# PSU.net
KiCad netlist of a schematic drawn in Altium Designer
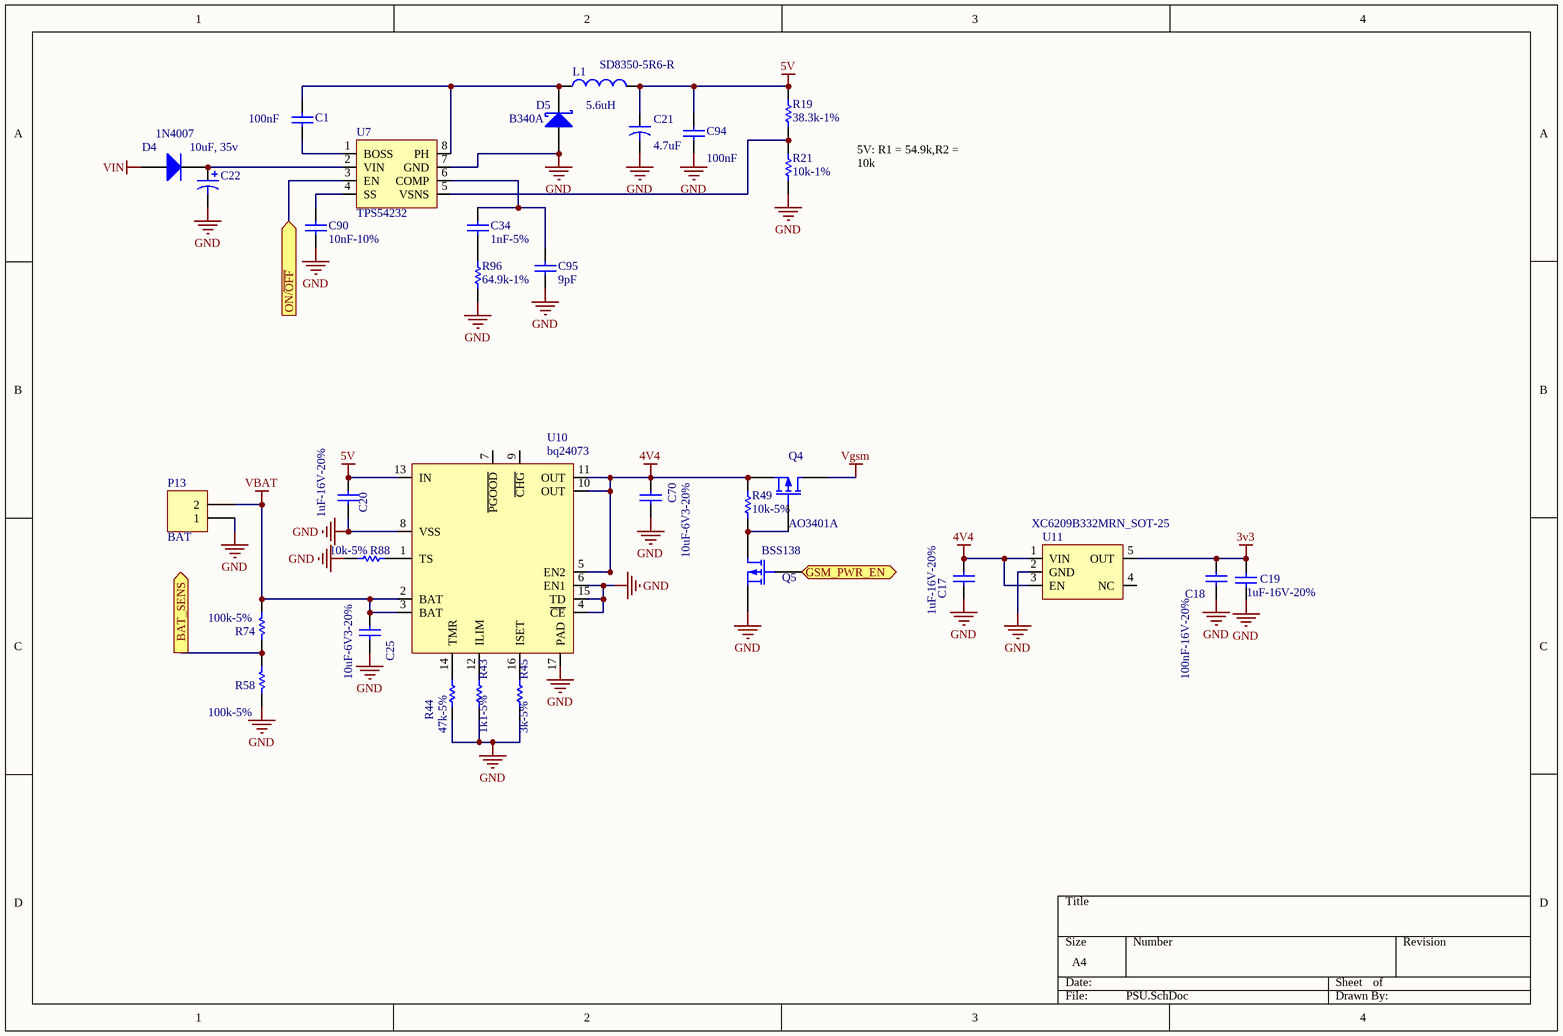
[diagram p0: PSU.SchDoc]

(export (version "E")
  (design (tool "Eeschema 10.0.6"))
  (components
    (comp (ref "C1")
      (value "100nF")
      (footprint "C0402")
      (description "Capacitor")
      (fields (field (name "PUBLISHER") "Altium Limited"))
      (libsource (lib "Miscellaneous Devices") (part "Cap"))
    )
    (comp (ref "C17")
      (value "1uF-16V-20%")
      (footprint "C0603")
      (description "CAP CER 1UF 16V Y5V 0603")
      (fields
        (field (name "MANUFACTURER") "Yageo")
        (field (name "DIGI-KEY PART NUMBER") "311-1372-1-ND")
        (field (name "PUBLISHER") "Altium Limited")
      )
      (libsource (lib "Miscellaneous Devices") (part "Cap"))
    )
    (comp (ref "C18")
      (value "100nF-16V-20%")
      (footprint "C0402")
      (description "CAP CER 0.1UF 16V Y5V 0402")
      (fields
        (field (name "MANUFACTURER") "Yageo")
        (field (name "DIGI-KEY PART NUMBER") "311-1047-1-ND")
        (field (name "PUBLISHER") "Altium Limited")
      )
      (libsource (lib "Miscellaneous Devices") (part "Cap"))
    )
    (comp (ref "C19")
      (value "1uF-16V-20%")
      (footprint "C0603")
      (description "CAP CER 1UF 16V Y5V 0603")
      (fields
        (field (name "MANUFACTURER") "Yageo")
        (field (name "DIGI-KEY PART NUMBER") "311-1372-1-ND")
        (field (name "PUBLISHER") "Altium Limited")
      )
      (libsource (lib "Miscellaneous Devices") (part "Cap"))
    )
    (comp (ref "C20")
      (value "1uF-16V-20%")
      (footprint "C0603")
      (description "CAP CER 1UF 16V Y5V 0603")
      (fields
        (field (name "MANUFACTURER") "Yageo")
        (field (name "DIGI-KEY PART NUMBER") "311-1372-1-ND")
        (field (name "PUBLISHER") "Altium Limited")
      )
      (libsource (lib "Miscellaneous Devices") (part "Cap"))
    )
    (comp (ref "C21")
      (value "4.7uF")
      (footprint "C1206")
      (description "Capacitor")
      (fields (field (name "PUBLISHER") "Altium Limited"))
      (libsource (lib "Miscellaneous Devices") (part "Cap2"))
    )
    (comp (ref "C22")
      (value "10uF, 35v")
      (footprint "CAPACITOR SIZE_C(D5.3)")
      (description "CAP ALUM 10UF 35V 20% SMD")
      (fields
        (field (name "DIGI-KEY PART NUMBER") "PCE3947TR-ND")
        (field (name "MANUFACTURER") "Panasonic Electronic Components")
        (field (name "PUBLISHER") "Altium Limited")
      )
      (libsource (lib "Miscellaneous Devices") (part "Cap Pol3"))
    )
    (comp (ref "C25")
      (value "10uF-6V3-20%")
      (footprint "C0603")
      (description "CAP CER 10UF 6.3V 20% X5R 0603")
      (fields
        (field (name "MANUFACTURER") "Yageo")
        (field (name "DIGI-KEY PART NUMBER") "311-1448-1-ND")
        (field (name "PUBLISHER") "Altium Limited")
      )
      (libsource (lib "Miscellaneous Devices") (part "Cap"))
    )
    (comp (ref "C34")
      (value "1nF-5%")
      (footprint "C0402")
      (description "Non-Polarized Capacitor")
      (fields (field (name "DIGI-KEY PART NUMBER") "311-1122-1-ND") (field (name "MANUFACTURER") "Yageo"))
      (libsource (lib "Capacitor") (part "1nF-50V-C0805"))
    )
    (comp (ref "C70")
      (value "10uF-6V3-20%")
      (footprint "C0603")
      (description "CAP CER 10UF 6.3V 20% X5R 0603")
      (fields
        (field (name "MANUFACTURER") "Yageo")
        (field (name "DIGI-KEY PART NUMBER") "311-1448-1-ND")
        (field (name "PUBLISHER") "Altium Limited")
      )
      (libsource (lib "Miscellaneous Devices") (part "Cap"))
    )
    (comp (ref "C90")
      (value "10nF-10%")
      (footprint "C0402")
      (description "Non-Polarized Capacitor")
      (fields (field (name "DIGI-KEY PART NUMBER") "311-1136-1-ND") (field (name "MANUFACTURER") "Yageo"))
      (libsource (lib "Capacitor") (part "10nF-50V-C0805"))
    )
    (comp (ref "C94")
      (value "100nF")
      (footprint "C0402")
      (description "Capacitor")
      (fields (field (name "PUBLISHER") "Altium Limited"))
      (libsource (lib "Miscellaneous Devices") (part "Cap"))
    )
    (comp (ref "C95")
      (value "9pF")
      (footprint "C0402")
      (description "Non-Polarized Capacitor")
      (fields (field (name "DIGI-KEY PART NUMBER") "311-1098-1-ND") (field (name "MANUFACTURER") "Yageo"))
      (libsource (lib "Capacitor") (part "9pF-50V-C0805"))
    )
    (comp (ref "D4")
      (value "1N4007")
      (footprint "DO-214AC (SMA)")
      (description "DIODE GEN PURPOSE 1000V 1A SMA")
      (fields
        (field (name "DIGI-KEY PART NUMBER") "641-1018-1-ND")
        (field (name "MANUFACTURER PART NUMBER") "CGRA4007-G")
        (field (name "PUBLISHER") "Altium Limited")
      )
      (libsource (lib "Miscellaneous Devices") (part "Diode"))
    )
    (comp (ref "D5")
      (value "B340A")
      (footprint "DO-214AC (SMA)")
      (description "DIODE SCHOTTKY 40V 3A SMA")
      (fields
        (field (name "DIGI-KEY PART NUMBER") "B340A-E3/61TGITR-ND")
        (field (name "MANUFACTURER PART NUMBER") "B340A-E3/61T")
        (field (name "PUBLISHER") "Altium Limited")
      )
      (libsource (lib "Miscellaneous Devices") (part "D Schottky"))
    )
    (comp (ref "L1")
      (value "SD8350-5R6-R")
      (footprint "SD8350-5R6-R")
      (description "Digikey part SD8350-4R7-R")
      (fields (field (name "ALTIUM_VALUE") "5.6uH") (field (name "PUBLISHER") "Altium Limited"))
      (libsource (lib "Miscellaneous Devices") (part "Inductor"))
    )
    (comp (ref "P13")
      (value "BAT")
      (footprint "HDR1X2")
      (description "Header, 2-Pin")
      (fields (field (name "PUBLISHER") "Altium Limited"))
      (libsource (lib "Miscellaneous Connectors") (part "Header 2"))
    )
    (comp (ref "Q4")
      (value "AO3401A")
      (footprint "SOT23-3")
      (description "MOSFET P-CH -30V -4.3A SOT23")
      (fields
        (field (name "DIGI-KEY PART NUMBER") "785-1001-1-ND")
        (field (name "MANUFACTURER") "Alpha & Omega Semiconductor Inc")
        (field (name "PUBLISHER") "Altium Limited")
      )
      (libsource (lib "") (part "MOSFET-P_1"))
    )
    (comp (ref "Q5")
      (value "BSS138")
      (footprint "SOT23-3")
      (description "MOSFET N-CH 50V 200MA SOT23-3")
      (fields
        (field (name "DIGI-KEY PART NUMBER") "BSS138-FDICT-ND")
        (field (name "MANUFACTURER") "Diodes Inc")
        (field (name "PUBLISHER") "Altium Limited")
      )
      (libsource (lib "Miscellaneous Devices") (part "MOSFET-P"))
    )
    (comp (ref "R19")
      (value "38.3k-1%")
      (footprint "R0402")
      (description "RES 38.3k OHM 1/4W 1% 0805 SMD")
      (fields (field (name "DIGI-KEY PART NUMBER") "311-38.3KCRTR-ND") (field (name "MANUFACTURER") "Yageo"))
      (libsource (lib "All_Resistor") (part "38.3k-1%-R0805"))
    )
    (comp (ref "R21")
      (value "10k-1%")
      (footprint "R0402")
      (description "RES 10k OHM 1/4W 1% 0805 SMD")
      (fields (field (name "DIGI-KEY PART NUMBER") "311-10.0KCRTR-ND") (field (name "MANUFACTURER") "Yageo"))
      (libsource (lib "All_Resistor") (part "10k-1%-R0805"))
    )
    (comp (ref "R43")
      (value "1k1-5%")
      (footprint "R0402")
      (description "RES 1.1K OHM 1/16W 5% 0402 SMD")
      (fields
        (field (name "DIGI-KEY PART NUMBER") "311-1.1KJRCT-ND")
        (field (name "MANUFACTURER") "Yageo")
        (field (name "PUBLISHER") "Altium Limited")
      )
      (libsource (lib "Miscellaneous Devices") (part "Res1"))
    )
    (comp (ref "R44")
      (value "47k-5%")
      (footprint "R0402")
      (description "RES 47K OHM 1/16W 5% 0402 SMD")
      (fields
        (field (name "DIGI-KEY PART NUMBER") "311-47KJRCT-ND")
        (field (name "MANUFACTURER") "Yageo")
        (field (name "PUBLISHER") "Altium Limited")
      )
      (libsource (lib "Miscellaneous Devices") (part "Res1"))
    )
    (comp (ref "R45")
      (value "3k-5%")
      (footprint "R0402")
      (description "RES 1.5K OHM 1/16W 5% 0402 SMD")
      (fields
        (field (name "DIGI-KEY PART NUMBER") "311-3.0KJRCT-ND")
        (field (name "MANUFACTURER") "Yageo")
        (field (name "PUBLISHER") "Altium Limited")
      )
      (libsource (lib "Miscellaneous Devices") (part "Res1"))
    )
    (comp (ref "R49")
      (value "10k-5%")
      (footprint "R0402")
      (description "RES 10K OHM 1/16W 5% 0402 SMD")
      (fields
        (field (name "DIGI-KEY PART NUMBER") "311-10KJRCT-ND")
        (field (name "MANUFACTURER") "Yageo")
        (field (name "PUBLISHER") "Altium Limited")
      )
      (libsource (lib "Miscellaneous Devices") (part "Res1"))
    )
    (comp (ref "R58")
      (value "100k-5%")
      (footprint "R0402")
      (description "RES 100K OHM 1/16W 5% 0402 SMD")
      (fields
        (field (name "DIGI-KEY PART NUMBER") "311-100KJRCT-ND")
        (field (name "MANUFACTURER") "Yageo")
        (field (name "PUBLISHER") "Altium Limited")
      )
      (libsource (lib "Miscellaneous Devices") (part "Res1"))
    )
    (comp (ref "R74")
      (value "100k-5%")
      (footprint "R0402")
      (description "RES 100K OHM 1/16W 5% 0402 SMD")
      (fields
        (field (name "DIGI-KEY PART NUMBER") "311-100KJRCT-ND")
        (field (name "MANUFACTURER") "Yageo")
        (field (name "PUBLISHER") "Altium Limited")
      )
      (libsource (lib "Miscellaneous Devices") (part "Res1"))
    )
    (comp (ref "R88")
      (value "10k-5%")
      (footprint "R0402")
      (description "RES 10K OHM 1/16W 5% 0402 SMD")
      (fields
        (field (name "DIGI-KEY PART NUMBER") "311-10KJRCT-ND")
        (field (name "MANUFACTURER") "Yageo")
        (field (name "PUBLISHER") "Altium Limited")
      )
      (libsource (lib "Miscellaneous Devices") (part "Res1"))
    )
    (comp (ref "R96")
      (value "64.9k-1%")
      (footprint "R0402")
      (description "RES 64.9k OHM 1/4W 1% 0805 SMD")
      (fields (field (name "DIGI-KEY PART NUMBER") "311-64.9KCRTR-ND") (field (name "MANUFACTURER") "Yageo"))
      (libsource (lib "All_Resistor") (part "64.9k-1%-R0805"))
    )
    (comp (ref "U7")
      (value "TPS54232")
      (footprint "SOIC127P600-8AL")
      (libsource (lib "TPS54232") (part "Component_1"))
    )
    (comp (ref "U10")
      (value "bq24073")
      (footprint "pq24073")
      (description "IC LI-ION CHARGE/PWR MGMT 16-QFN")
      (fields
        (field (name "DIGI-KEY PART NUMBER") "296-23839-1-ND")
        (field (name "MANUFACTURER") "Texas Instruments")
      )
      (libsource (lib "TI_Power") (part "BATTERY_CHARGER"))
    )
    (comp (ref "U11")
      (value "XC6209B332MRN_SOT-25")
      (footprint "SOT23-5")
      (fields (field (name "MANUFACTURER") "Tyrone"))
      (libsource (lib "Schlib1") (part "XC6209B332MRN_SOT-25"))
    )
  )
  (nets
    (net (code "1") (name "/BAT_SENS") (class "Default")
      (node (ref "R58") (pin "2") (pinfunction "2_2") (pintype "passive"))
      (node (ref "R74") (pin "1") (pinfunction "1_1") (pintype "passive"))
    )
    (net (code "2") (name "/GSM_PWR_EN") (class "Default")
      (node (ref "Q5") (pin "1") (pinfunction "G_1") (pintype "passive"))
    )
    (net (code "3") (name "/ON{slash}~{OFF}") (class "Default")
      (node (ref "U7") (pin "3") (pinfunction "EN_3") (pintype "passive"))
    )
    (net (code "4") (name "3v3") (class "Default")
      (node (ref "C18") (pin "2") (pinfunction "2_2") (pintype "passive"))
      (node (ref "C19") (pin "1") (pinfunction "1_1") (pintype "passive"))
      (node (ref "U11") (pin "5") (pinfunction "OUT_5") (pintype "passive"))
    )
    (net (code "5") (name "4V4") (class "Default")
      (node (ref "C17") (pin "1") (pinfunction "1_1") (pintype "passive"))
      (node (ref "C70") (pin "2") (pinfunction "2_2") (pintype "passive"))
      (node (ref "Q4") (pin "2") (pinfunction "S_2") (pintype "passive"))
      (node (ref "R49") (pin "1") (pinfunction "1_1") (pintype "passive"))
      (node (ref "U10") (pin "10") (pinfunction "OUT_10") (pintype "passive"))
      (node (ref "U10") (pin "11") (pinfunction "OUT_11") (pintype "passive"))
      (node (ref "U10") (pin "5") (pinfunction "EN2_5") (pintype "passive"))
      (node (ref "U11") (pin "1") (pinfunction "VIN_1") (pintype "passive"))
      (node (ref "U11") (pin "3") (pinfunction "EN_3") (pintype "passive"))
    )
    (net (code "6") (name "5V") (class "Default")
      (node (ref "C20") (pin "2") (pinfunction "2_2") (pintype "passive"))
      (node (ref "C21") (pin "1") (pinfunction "1_1") (pintype "passive"))
      (node (ref "C94") (pin "2") (pinfunction "2_2") (pintype "passive"))
      (node (ref "L1") (pin "2") (pinfunction "2_2") (pintype "passive"))
      (node (ref "R19") (pin "2") (pinfunction "2_2") (pintype "passive"))
      (node (ref "U10") (pin "13") (pinfunction "IN_13") (pintype "passive"))
    )
    (net (code "7") (name "GND") (class "Default")
      (node (ref "C17") (pin "2") (pinfunction "2_2") (pintype "passive"))
      (node (ref "C18") (pin "1") (pinfunction "1_1") (pintype "passive"))
      (node (ref "C19") (pin "2") (pinfunction "2_2") (pintype "passive"))
      (node (ref "C20") (pin "1") (pinfunction "1_1") (pintype "passive"))
      (node (ref "C21") (pin "2") (pinfunction "2_2") (pintype "passive"))
      (node (ref "C22") (pin "2") (pinfunction "2_2") (pintype "passive"))
      (node (ref "C25") (pin "1") (pinfunction "1_1") (pintype "passive"))
      (node (ref "C70") (pin "1") (pinfunction "1_1") (pintype "passive"))
      (node (ref "C90") (pin "1") (pinfunction "1_1") (pintype "passive"))
      (node (ref "C94") (pin "1") (pinfunction "1_1") (pintype "passive"))
      (node (ref "C95") (pin "1") (pinfunction "1_1") (pintype "passive"))
      (node (ref "D5") (pin "1") (pinfunction "A_1") (pintype "passive"))
      (node (ref "P13") (pin "1") (pinfunction "1_1") (pintype "passive"))
      (node (ref "Q5") (pin "2") (pinfunction "S_2") (pintype "passive"))
      (node (ref "R21") (pin "1") (pinfunction "1_1") (pintype "passive"))
      (node (ref "R43") (pin "2") (pinfunction "2_2") (pintype "passive"))
      (node (ref "R44") (pin "2") (pinfunction "2_2") (pintype "passive"))
      (node (ref "R45") (pin "2") (pinfunction "2_2") (pintype "passive"))
      (node (ref "R58") (pin "1") (pinfunction "1_1") (pintype "passive"))
      (node (ref "R88") (pin "2") (pinfunction "2_2") (pintype "passive"))
      (node (ref "R96") (pin "1") (pinfunction "1_1") (pintype "passive"))
      (node (ref "U10") (pin "15") (pinfunction "TD_15") (pintype "passive"))
      (node (ref "U10") (pin "17") (pinfunction "PAD_17") (pintype "passive"))
      (node (ref "U10") (pin "4") (pinfunction "~{CE}_4") (pintype "passive"))
      (node (ref "U10") (pin "6") (pinfunction "EN1_6") (pintype "passive"))
      (node (ref "U10") (pin "8") (pinfunction "VSS_8") (pintype "passive"))
      (node (ref "U11") (pin "2") (pinfunction "GND_2") (pintype "passive"))
      (node (ref "U7") (pin "7") (pinfunction "GND_7") (pintype "passive"))
    )
    (net (code "8") (name "Net-(C34-Pad1)") (class "Default")
      (node (ref "C34") (pin "1") (pinfunction "1_1") (pintype "passive"))
      (node (ref "R96") (pin "2") (pinfunction "2_2") (pintype "passive"))
    )
    (net (code "9") (name "Net-(D4-K)") (class "Default")
      (node (ref "C22") (pin "1") (pinfunction "1_1") (pintype "passive"))
      (node (ref "D4") (pin "2") (pinfunction "K_2") (pintype "passive"))
      (node (ref "U7") (pin "2") (pinfunction "VIN_2") (pintype "passive"))
    )
    (net (code "10") (name "Net-(D5-K)") (class "Default")
      (node (ref "C1") (pin "1") (pinfunction "1_1") (pintype "passive"))
      (node (ref "D5") (pin "2") (pinfunction "K_2") (pintype "passive"))
      (node (ref "L1") (pin "1") (pinfunction "1_1") (pintype "passive"))
      (node (ref "U7") (pin "8") (pinfunction "PH_8") (pintype "passive"))
    )
    (net (code "11") (name "Net-(Q4-G)") (class "Default")
      (node (ref "Q4") (pin "1") (pinfunction "G_1") (pintype "passive"))
      (node (ref "Q5") (pin "3") (pinfunction "D_3") (pintype "passive"))
      (node (ref "R49") (pin "2") (pinfunction "2_2") (pintype "passive"))
    )
    (net (code "12") (name "Net-(U7-BOSS)") (class "Default")
      (node (ref "C1") (pin "2") (pinfunction "2_2") (pintype "passive"))
      (node (ref "U7") (pin "1") (pinfunction "BOSS_1") (pintype "passive"))
    )
    (net (code "13") (name "Net-(U7-COMP)") (class "Default")
      (node (ref "C34") (pin "2") (pinfunction "2_2") (pintype "passive"))
      (node (ref "C95") (pin "2") (pinfunction "2_2") (pintype "passive"))
      (node (ref "U7") (pin "6") (pinfunction "COMP_6") (pintype "passive"))
    )
    (net (code "14") (name "Net-(U7-SS)") (class "Default")
      (node (ref "C90") (pin "2") (pinfunction "2_2") (pintype "passive"))
      (node (ref "U7") (pin "4") (pinfunction "SS_4") (pintype "passive"))
    )
    (net (code "15") (name "Net-(U7-VSNS)") (class "Default")
      (node (ref "R19") (pin "1") (pinfunction "1_1") (pintype "passive"))
      (node (ref "R21") (pin "2") (pinfunction "2_2") (pintype "passive"))
      (node (ref "U7") (pin "5") (pinfunction "VSNS_5") (pintype "passive"))
    )
    (net (code "16") (name "Net-(U10-ILIM)") (class "Default")
      (node (ref "R43") (pin "1") (pinfunction "1_1") (pintype "passive"))
      (node (ref "U10") (pin "12") (pinfunction "ILIM_12") (pintype "passive"))
    )
    (net (code "17") (name "Net-(U10-ISET)") (class "Default")
      (node (ref "R45") (pin "1") (pinfunction "1_1") (pintype "passive"))
      (node (ref "U10") (pin "16") (pinfunction "ISET_16") (pintype "passive"))
    )
    (net (code "18") (name "Net-(U10-TMR)") (class "Default")
      (node (ref "R44") (pin "1") (pinfunction "1_1") (pintype "passive"))
      (node (ref "U10") (pin "14") (pinfunction "TMR_14") (pintype "passive"))
    )
    (net (code "19") (name "Net-(U10-TS)") (class "Default")
      (node (ref "R88") (pin "1") (pinfunction "1_1") (pintype "passive"))
      (node (ref "U10") (pin "1") (pinfunction "TS_1") (pintype "passive"))
    )
    (net (code "20") (name "VBAT") (class "Default")
      (node (ref "C25") (pin "2") (pinfunction "2_2") (pintype "passive"))
      (node (ref "P13") (pin "2") (pinfunction "2_2") (pintype "passive"))
      (node (ref "R74") (pin "2") (pinfunction "2_2") (pintype "passive"))
      (node (ref "U10") (pin "2") (pinfunction "BAT_2") (pintype "passive"))
      (node (ref "U10") (pin "3") (pinfunction "BAT_3") (pintype "passive"))
    )
    (net (code "21") (name "VIN") (class "Default")
      (node (ref "D4") (pin "1") (pinfunction "A_1") (pintype "passive"))
    )
    (net (code "22") (name "Vgsm") (class "Default")
      (node (ref "Q4") (pin "3") (pinfunction "D_3") (pintype "passive"))
    )
    (net (code "23") (name "unconnected-(U10-~{CHG}-Pad9)") (class "Default")
      (node (ref "U10") (pin "9") (pinfunction "~{CHG}_9") (pintype "passive"))
    )
    (net (code "24") (name "unconnected-(U10-~{PGOOD}-Pad7)") (class "Default")
      (node (ref "U10") (pin "7") (pinfunction "~{PGOOD}_7") (pintype "passive"))
    )
    (net (code "25") (name "unconnected-(U11-NC-Pad4)") (class "Default")
      (node (ref "U11") (pin "4") (pinfunction "NC_4") (pintype "passive"))
    )
  )
)
